# CryptoFlashRTC.net
KiCad netlist of a schematic drawn in EAGLE
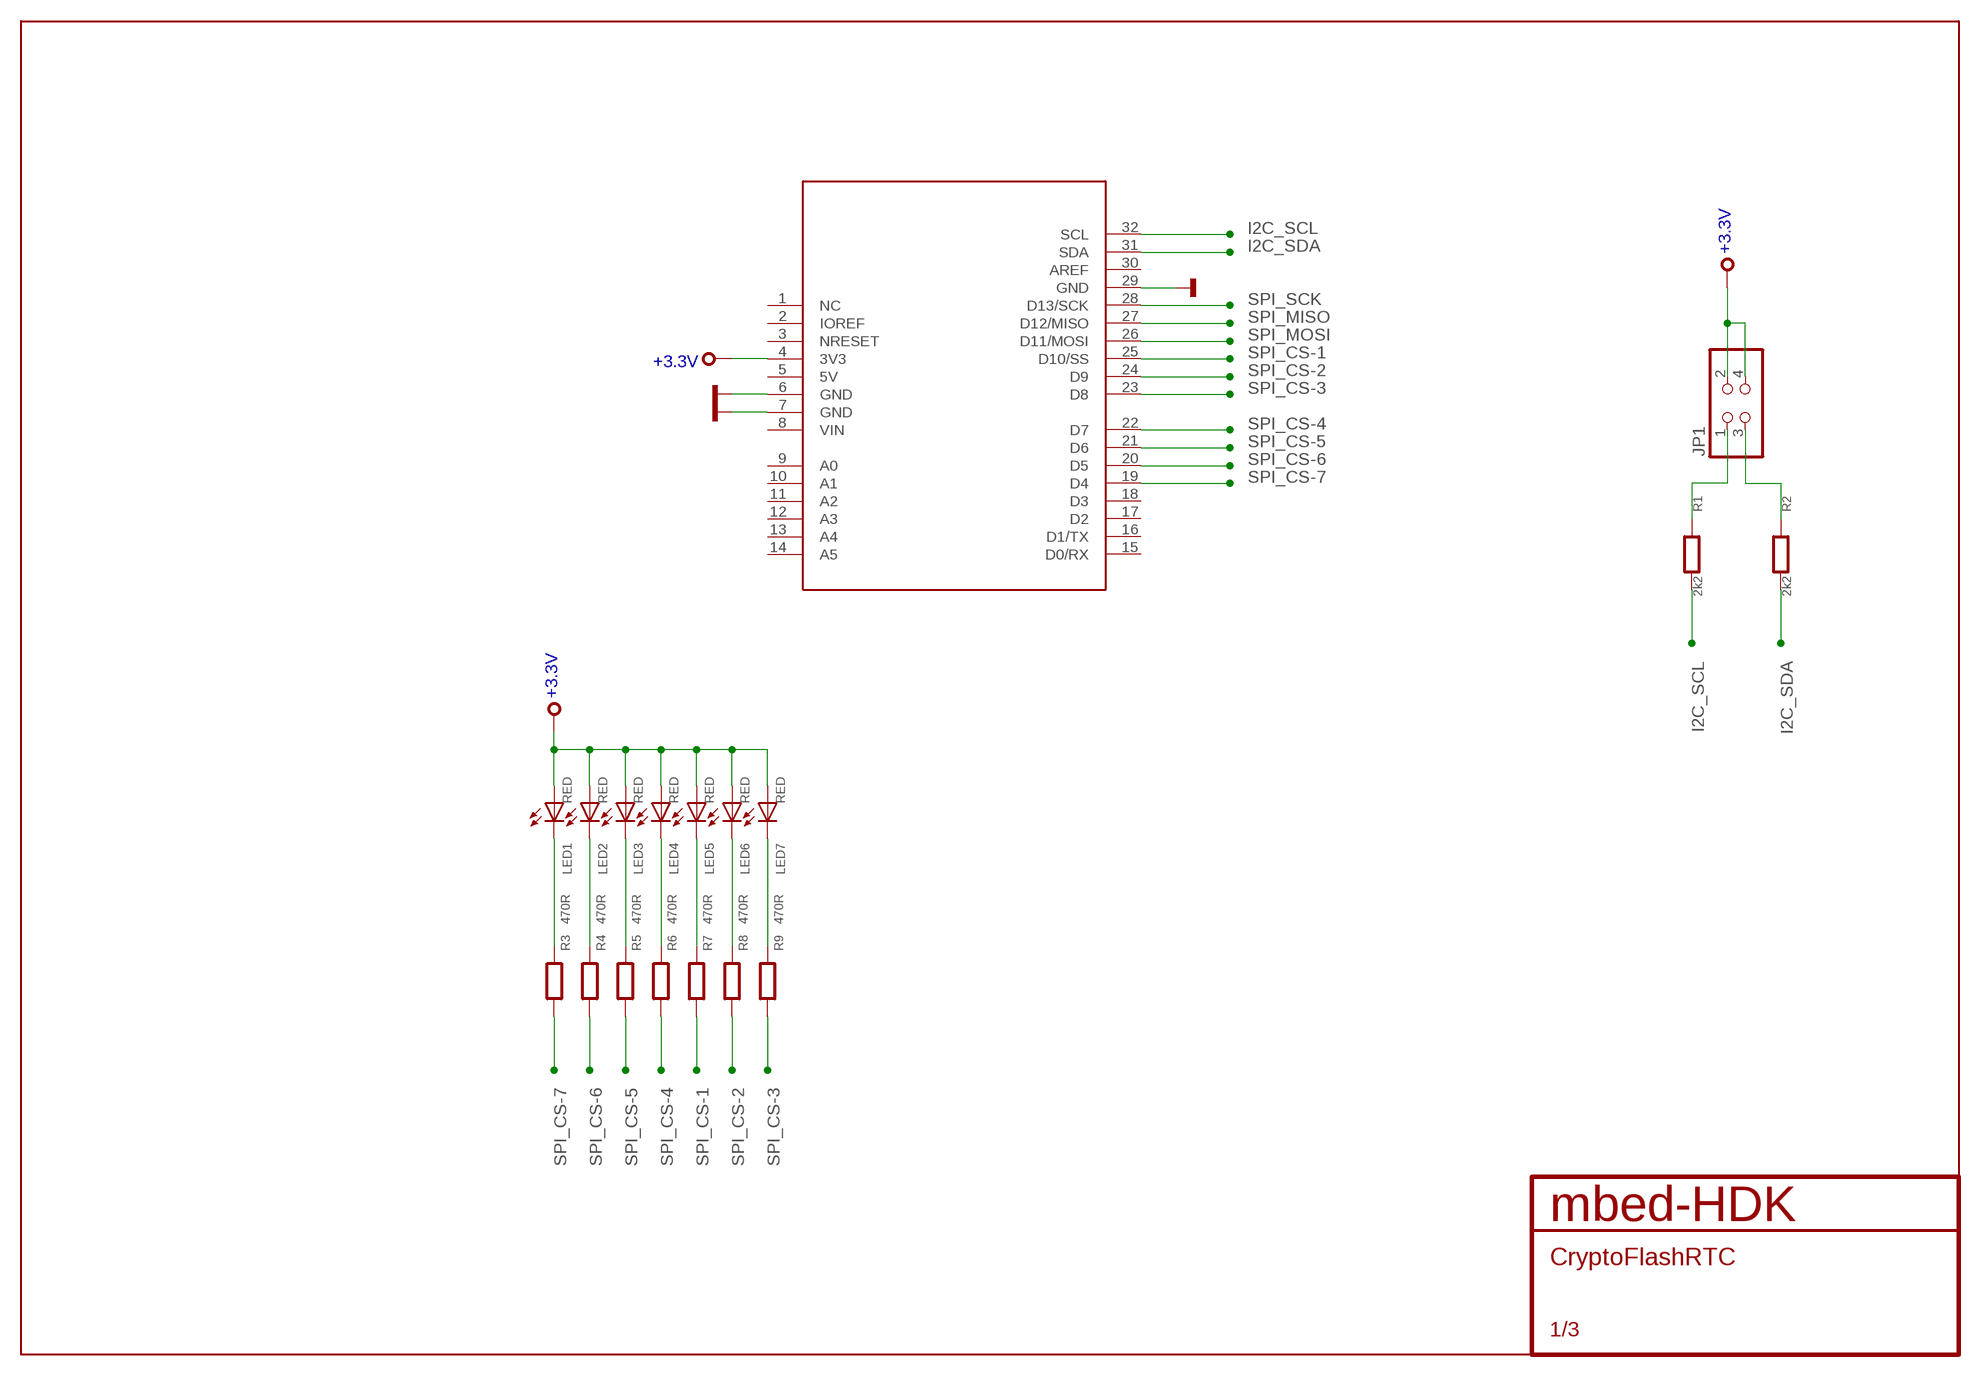
[diagram p0: schematic, sheet 1]
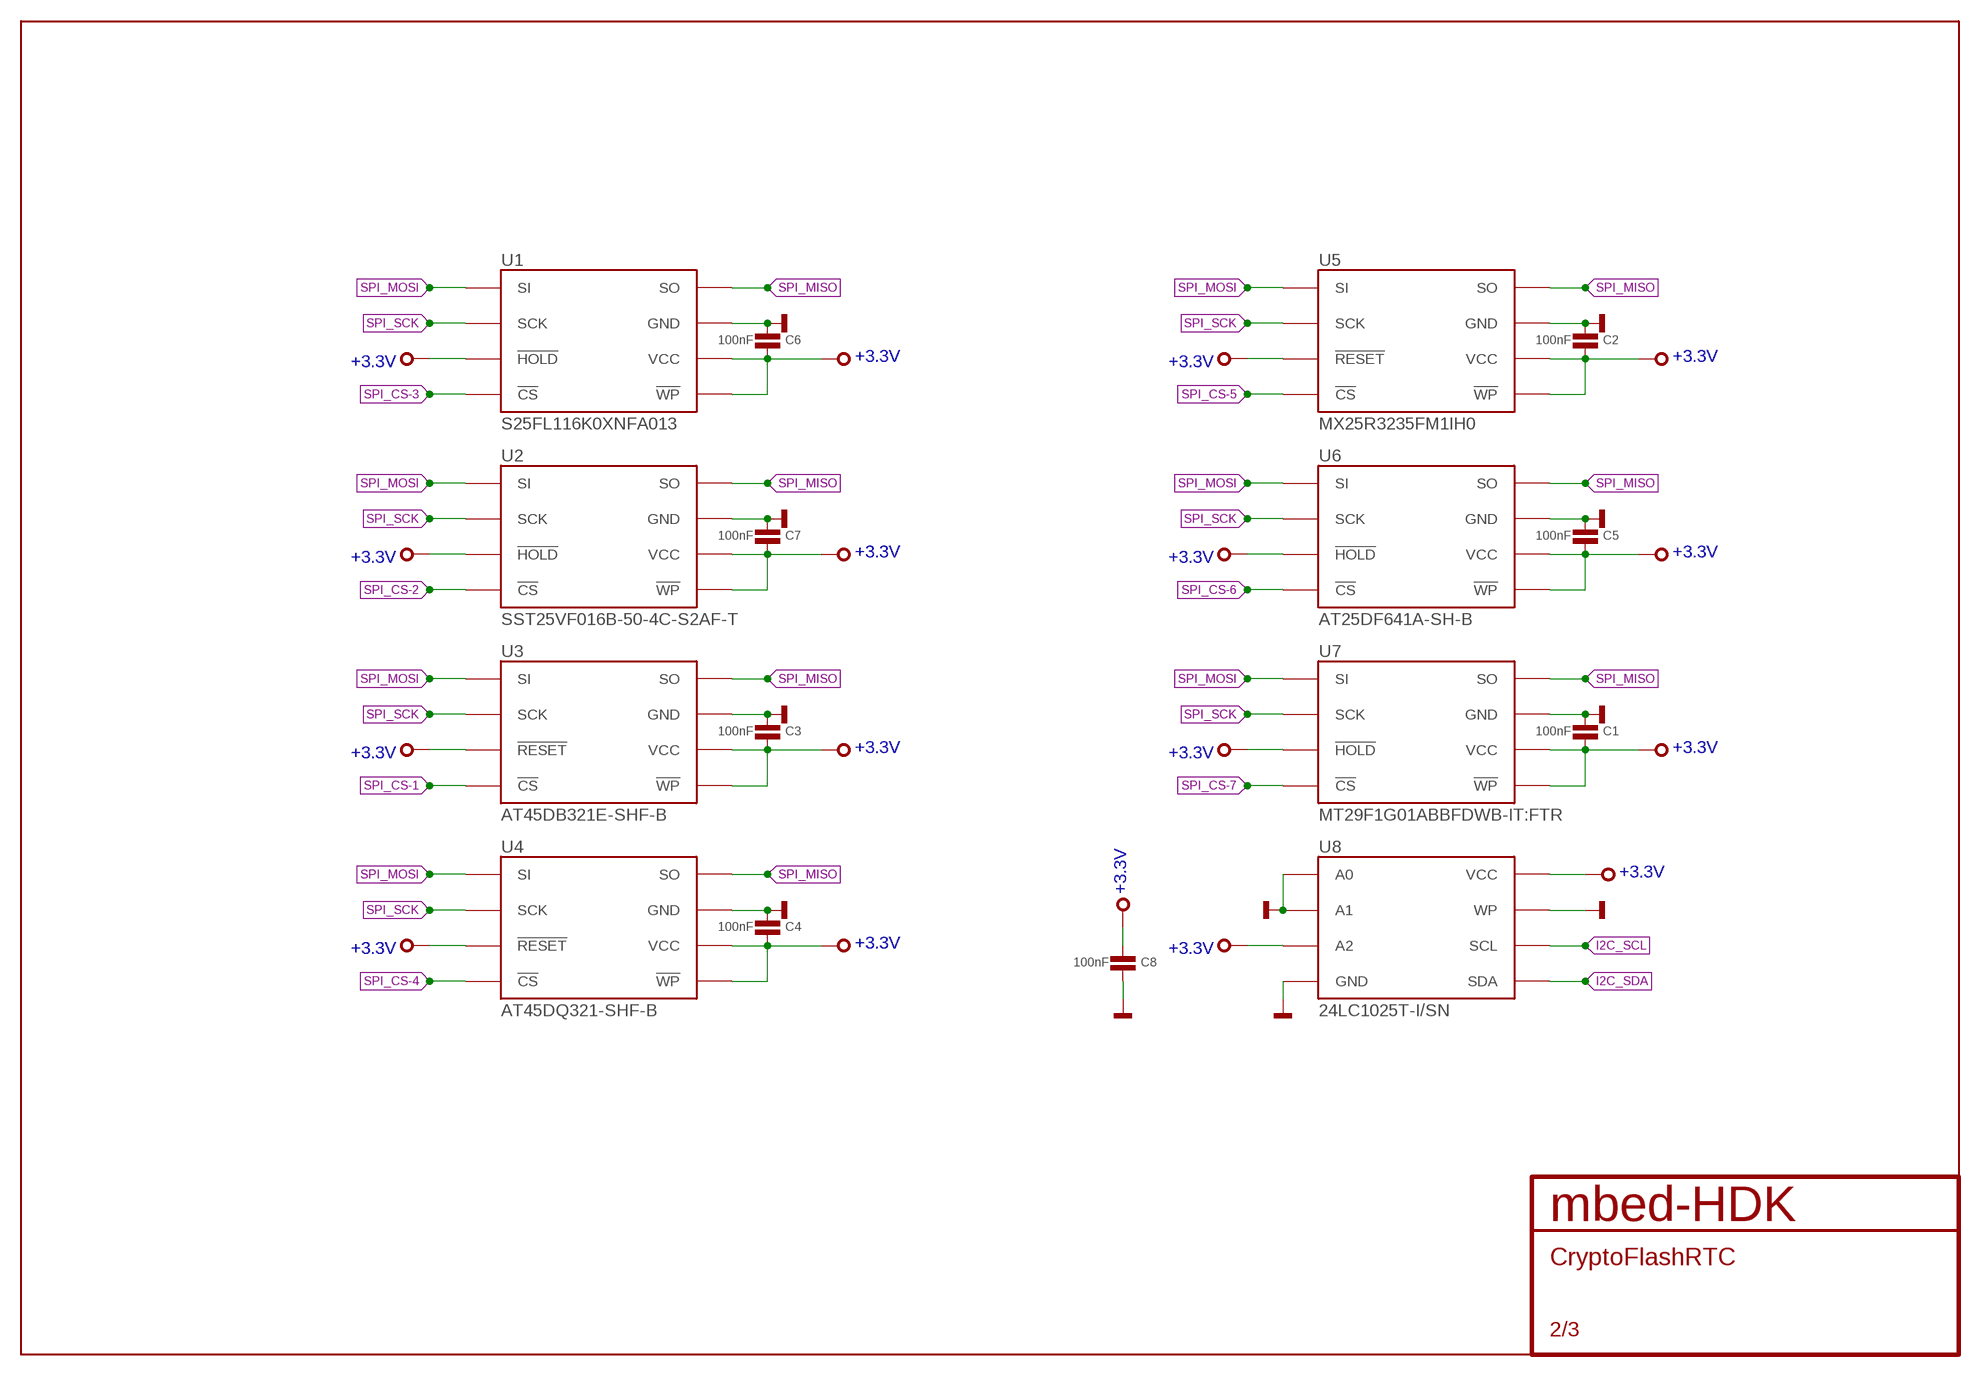
[diagram p1: schematic, sheet 2]
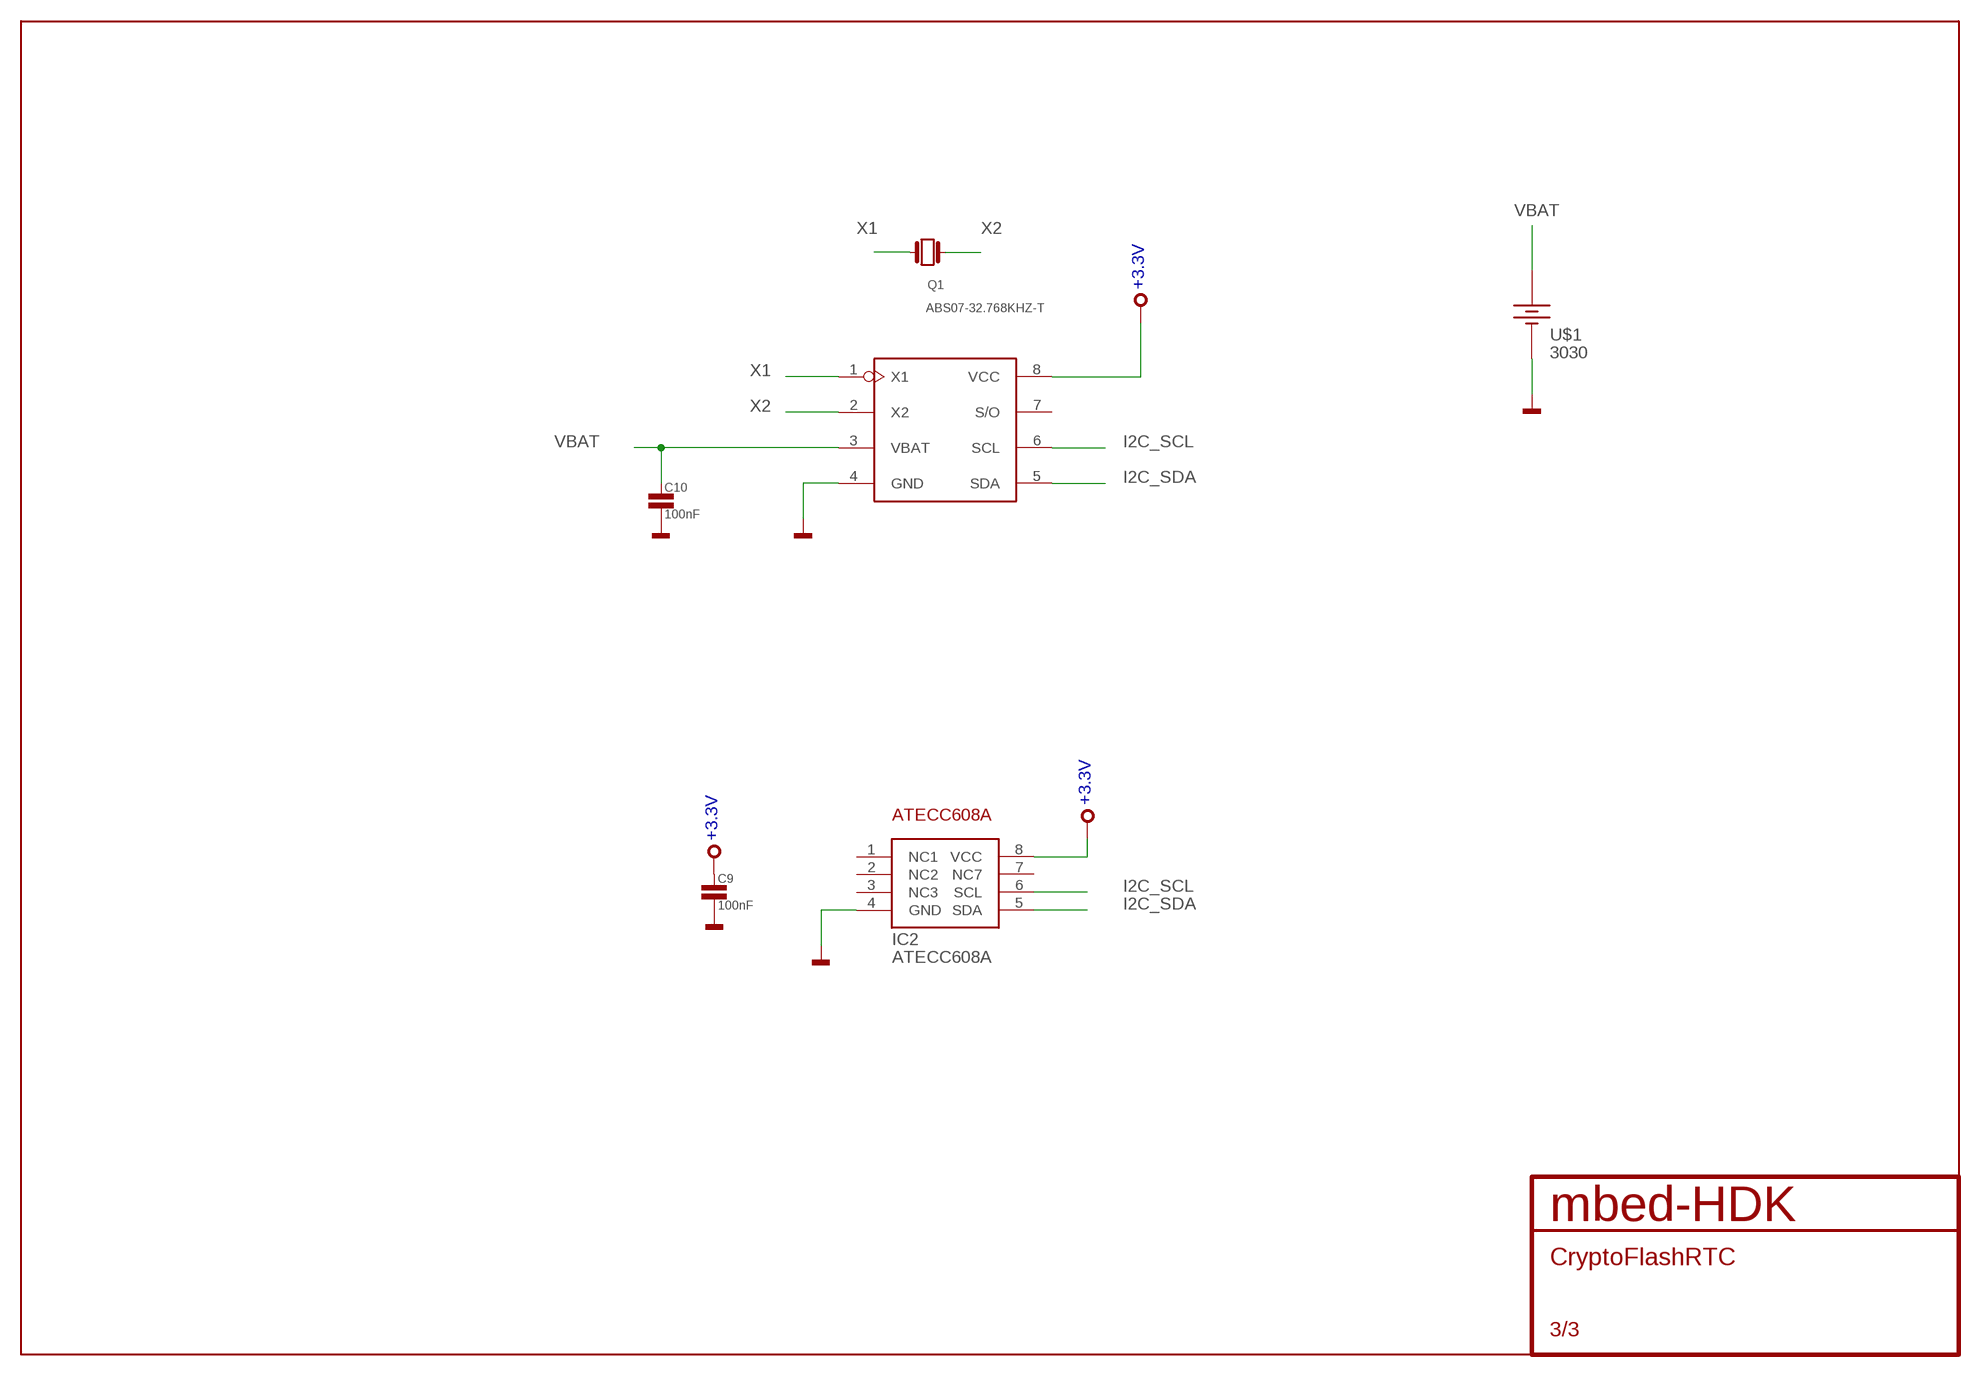
[diagram p2: schematic, sheet 3]

(export (version "E")
  (design (tool "Eeschema 10.0.6"))
  (components
    (comp (ref "C9")
      (value "100nF")
      (footprint "eagle-import:0603")
      (libsource (lib "eagle-import") (part "C0603"))
    )
    (comp (ref "C10")
      (value "100nF")
      (footprint "eagle-import:0603")
      (libsource (lib "eagle-import") (part "C0603"))
    )
    (comp (ref "IC2")
      (value "ATECC608A")
      (footprint "eagle-import:SO8")
      (libsource (lib "eagle-import") (part "ATECC608A"))
    )
    (comp (ref "Q1")
      (value "ABS07-32.768KHZ-T")
      (footprint "eagle-import:FC135")
      (fields (field (name "MF") "Abracon"))
      (libsource (lib "eagle-import") (part "ABS07-32.768KHZ-T"))
    )
    (comp (ref "U$1")
      (value "3030")
      (footprint "eagle-import:3030")
      (fields (field (name "MF") "Keystone"))
      (libsource (lib "eagle-import") (part "3030"))
    )
    (comp (ref "U9")
      (value "DS1307")
      (footprint "eagle-import:SO08")
      (libsource (lib "eagle-import") (part "DS1307"))
    )
    (comp (ref "C1")
      (value "100nF")
      (footprint "eagle-import:0603")
      (libsource (lib "eagle-import") (part "C0603"))
    )
    (comp (ref "C2")
      (value "100nF")
      (footprint "eagle-import:0603")
      (libsource (lib "eagle-import") (part "C0603"))
    )
    (comp (ref "C3")
      (value "100nF")
      (footprint "eagle-import:0603")
      (libsource (lib "eagle-import") (part "C0603"))
    )
    (comp (ref "C4")
      (value "100nF")
      (footprint "eagle-import:0603")
      (libsource (lib "eagle-import") (part "C0603"))
    )
    (comp (ref "C5")
      (value "100nF")
      (footprint "eagle-import:0603")
      (libsource (lib "eagle-import") (part "C0603"))
    )
    (comp (ref "C6")
      (value "100nF")
      (footprint "eagle-import:0603")
      (libsource (lib "eagle-import") (part "C0603"))
    )
    (comp (ref "C7")
      (value "100nF")
      (footprint "eagle-import:0603")
      (libsource (lib "eagle-import") (part "C0603"))
    )
    (comp (ref "C8")
      (value "100nF")
      (footprint "eagle-import:0603")
      (libsource (lib "eagle-import") (part "C0603"))
    )
    (comp (ref "U1")
      (value "S25FL116K0XNFA013")
      (footprint "eagle-import:SO8-WIDE@1")
      (fields (field (name "MF") "Cypress Semiconductor Corp"))
      (libsource (lib "eagle-import") (part "S25FL116K0XNFA013"))
    )
    (comp (ref "U2")
      (value "SST25VF016B-50-4C-S2AF-T")
      (footprint "eagle-import:SO8-WIDE")
      (fields (field (name "MF") "Microchip"))
      (libsource (lib "eagle-import") (part "SST25VF016B-50-4C-S2AF-T"))
    )
    (comp (ref "U3")
      (value "AT45DB321E-SHF-B")
      (footprint "eagle-import:SO8-WIDE")
      (fields (field (name "MF") "Adesto Technologies"))
      (libsource (lib "eagle-import") (part "AT45DB321E-SHF-B"))
    )
    (comp (ref "U4")
      (value "AT45DQ321-SHF-B")
      (footprint "eagle-import:SO8-WIDE")
      (fields (field (name "MF") "Adesto Technologies"))
      (libsource (lib "eagle-import") (part "AT45DQ321-SHF-B"))
    )
    (comp (ref "U5")
      (value "MX25R3235FM1IH0")
      (footprint "eagle-import:SO8")
      (fields (field (name "MF") "Macronix"))
      (libsource (lib "eagle-import") (part "MX25R3235FM1IH0"))
    )
    (comp (ref "U6")
      (value "AT25DF641A-SH-B")
      (footprint "eagle-import:SO8-WIDE")
      (fields (field (name "MF") "Adesto Technologies"))
      (libsource (lib "eagle-import") (part "AT25DF641A-SH-B"))
    )
    (comp (ref "U7")
      (value "MT29F1G01ABBFDWB-IT:FTR")
      (footprint "eagle-import:8-U-PDFN")
      (fields (field (name "MF") "Micron Technology Inc."))
      (libsource (lib "eagle-import") (part "MT29F1G01ABBFDWB-IT{colon}FTR"))
    )
    (comp (ref "U8")
      (value "24LC1025T-I/SN")
      (footprint "eagle-import:SO8")
      (fields (field (name "MF") "Microchip Technology"))
      (libsource (lib "eagle-import") (part "24LC1025T-I/SN"))
    )
    (comp (ref "BRD1")
      (value "K64F/K22F-SHIELD")
      (footprint "eagle-import:K64F_K22F")
      (libsource (lib "eagle-import") (part "K64F/K22F-SHIELD"))
    )
    (comp (ref "JP1")
      (value "PINHD-2X2")
      (footprint "eagle-import:2X02")
      (libsource (lib "eagle-import") (part "PINHD-2X2"))
    )
    (comp (ref "LED1")
      (value "RED")
      (footprint "eagle-import:CHIPLED_0603")
      (fields (field (name "MF") "Wurth Electronics Inc"))
      (libsource (lib "eagle-import") (part "SMD_LED0603"))
    )
    (comp (ref "LED2")
      (value "RED")
      (footprint "eagle-import:CHIPLED_0603")
      (fields (field (name "MF") "Wurth Electronics Inc"))
      (libsource (lib "eagle-import") (part "SMD_LED0603"))
    )
    (comp (ref "LED3")
      (value "RED")
      (footprint "eagle-import:CHIPLED_0603")
      (fields (field (name "MF") "Wurth Electronics Inc"))
      (libsource (lib "eagle-import") (part "SMD_LED0603"))
    )
    (comp (ref "LED4")
      (value "RED")
      (footprint "eagle-import:CHIPLED_0603")
      (fields (field (name "MF") "Wurth Electronics Inc"))
      (libsource (lib "eagle-import") (part "SMD_LED0603"))
    )
    (comp (ref "LED5")
      (value "RED")
      (footprint "eagle-import:CHIPLED_0603")
      (fields (field (name "MF") "Wurth Electronics Inc"))
      (libsource (lib "eagle-import") (part "SMD_LED0603"))
    )
    (comp (ref "LED6")
      (value "RED")
      (footprint "eagle-import:CHIPLED_0603")
      (fields (field (name "MF") "Wurth Electronics Inc"))
      (libsource (lib "eagle-import") (part "SMD_LED0603"))
    )
    (comp (ref "LED7")
      (value "RED")
      (footprint "eagle-import:CHIPLED_0603")
      (fields (field (name "MF") "Wurth Electronics Inc"))
      (libsource (lib "eagle-import") (part "SMD_LED0603"))
    )
    (comp (ref "R1")
      (value "2k2")
      (footprint "eagle-import:0603")
      (libsource (lib "eagle-import") (part "R0603"))
    )
    (comp (ref "R2")
      (value "2k2")
      (footprint "eagle-import:0603")
      (libsource (lib "eagle-import") (part "R0603"))
    )
    (comp (ref "R3")
      (value "470R")
      (footprint "eagle-import:0603")
      (libsource (lib "eagle-import") (part "R0603"))
    )
    (comp (ref "R4")
      (value "470R")
      (footprint "eagle-import:0603")
      (libsource (lib "eagle-import") (part "R0603"))
    )
    (comp (ref "R5")
      (value "470R")
      (footprint "eagle-import:0603")
      (libsource (lib "eagle-import") (part "R0603"))
    )
    (comp (ref "R6")
      (value "470R")
      (footprint "eagle-import:0603")
      (libsource (lib "eagle-import") (part "R0603"))
    )
    (comp (ref "R7")
      (value "470R")
      (footprint "eagle-import:0603")
      (libsource (lib "eagle-import") (part "R0603"))
    )
    (comp (ref "R8")
      (value "470R")
      (footprint "eagle-import:0603")
      (libsource (lib "eagle-import") (part "RESISTOR0603"))
    )
    (comp (ref "R9")
      (value "470R")
      (footprint "eagle-import:0603")
      (libsource (lib "eagle-import") (part "R0603"))
    )
  )
  (nets
    (net (code "1") (name "+3.3V") (class "Default")
      (node (ref "BRD1") (pin "4") (pinfunction "3V3_4") (pintype "bidirectional"))
      (node (ref "C1") (pin "1") (pinfunction "P$1_1") (pintype "passive"))
      (node (ref "C2") (pin "1") (pinfunction "P$1_1") (pintype "passive"))
      (node (ref "C3") (pin "1") (pinfunction "P$1_1") (pintype "passive"))
      (node (ref "C4") (pin "1") (pinfunction "P$1_1") (pintype "passive"))
      (node (ref "C5") (pin "1") (pinfunction "P$1_1") (pintype "passive"))
      (node (ref "C6") (pin "1") (pinfunction "P$1_1") (pintype "passive"))
      (node (ref "C7") (pin "1") (pinfunction "P$1_1") (pintype "passive"))
      (node (ref "C8") (pin "2") (pinfunction "P$2_2") (pintype "passive"))
      (node (ref "C9") (pin "1") (pinfunction "P$1_1") (pintype "passive"))
      (node (ref "IC2") (pin "8") (pinfunction "VCC_8") (pintype "bidirectional"))
      (node (ref "JP1") (pin "2") (pinfunction "2_2") (pintype "passive"))
      (node (ref "JP1") (pin "4") (pinfunction "4_4") (pintype "passive"))
      (node (ref "LED1") (pin "A") (pinfunction "A_A") (pintype "passive"))
      (node (ref "LED2") (pin "A") (pinfunction "A_A") (pintype "passive"))
      (node (ref "LED3") (pin "A") (pinfunction "A_A") (pintype "passive"))
      (node (ref "LED4") (pin "A") (pinfunction "A_A") (pintype "passive"))
      (node (ref "LED5") (pin "A") (pinfunction "A_A") (pintype "passive"))
      (node (ref "LED6") (pin "A") (pinfunction "A_A") (pintype "passive"))
      (node (ref "LED7") (pin "A") (pinfunction "A_A") (pintype "passive"))
      (node (ref "U1") (pin "3") (pinfunction "~{WP}_3") (pintype "bidirectional"))
      (node (ref "U1") (pin "7") (pinfunction "~{HOLD}_7") (pintype "bidirectional"))
      (node (ref "U1") (pin "8") (pinfunction "VCC_8") (pintype "bidirectional"))
      (node (ref "U2") (pin "3") (pinfunction "~{WP}_3") (pintype "bidirectional"))
      (node (ref "U2") (pin "7") (pinfunction "~{HOLD}_7") (pintype "bidirectional"))
      (node (ref "U2") (pin "8") (pinfunction "VCC_8") (pintype "bidirectional"))
      (node (ref "U3") (pin "3") (pinfunction "~{RESET}_3") (pintype "bidirectional"))
      (node (ref "U3") (pin "5") (pinfunction "~{WP}_5") (pintype "bidirectional"))
      (node (ref "U3") (pin "6") (pinfunction "VCC_6") (pintype "bidirectional"))
      (node (ref "U4") (pin "3") (pinfunction "~{RESET}_3") (pintype "bidirectional"))
      (node (ref "U4") (pin "5") (pinfunction "~{WP}_5") (pintype "bidirectional"))
      (node (ref "U4") (pin "6") (pinfunction "VCC_6") (pintype "bidirectional"))
      (node (ref "U5") (pin "3") (pinfunction "~{WP}_3") (pintype "bidirectional"))
      (node (ref "U5") (pin "7") (pinfunction "~{RESET}_7") (pintype "bidirectional"))
      (node (ref "U5") (pin "8") (pinfunction "VCC_8") (pintype "bidirectional"))
      (node (ref "U6") (pin "3") (pinfunction "~{WP}_3") (pintype "bidirectional"))
      (node (ref "U6") (pin "7") (pinfunction "~{HOLD}_7") (pintype "bidirectional"))
      (node (ref "U6") (pin "8") (pinfunction "VCC_8") (pintype "bidirectional"))
      (node (ref "U7") (pin "3") (pinfunction "~{WP}_3") (pintype "bidirectional"))
      (node (ref "U7") (pin "7") (pinfunction "~{HOLD}_7") (pintype "bidirectional"))
      (node (ref "U7") (pin "8") (pinfunction "VCC_8") (pintype "bidirectional"))
      (node (ref "U8") (pin "3") (pinfunction "A2_3") (pintype "bidirectional"))
      (node (ref "U8") (pin "8") (pinfunction "VCC_8") (pintype "bidirectional"))
      (node (ref "U9") (pin "8") (pinfunction "VCC_8") (pintype "bidirectional"))
    )
    (net (code "2") (name "GND") (class "Default")
      (node (ref "BRD1") (pin "29") (pinfunction "GND_29") (pintype "bidirectional"))
      (node (ref "BRD1") (pin "6") (pinfunction "GND_6") (pintype "bidirectional"))
      (node (ref "BRD1") (pin "7") (pinfunction "GND_7") (pintype "bidirectional"))
      (node (ref "C1") (pin "2") (pinfunction "P$2_2") (pintype "passive"))
      (node (ref "C10") (pin "2") (pinfunction "P$2_2") (pintype "passive"))
      (node (ref "C2") (pin "2") (pinfunction "P$2_2") (pintype "passive"))
      (node (ref "C3") (pin "2") (pinfunction "P$2_2") (pintype "passive"))
      (node (ref "C4") (pin "2") (pinfunction "P$2_2") (pintype "passive"))
      (node (ref "C5") (pin "2") (pinfunction "P$2_2") (pintype "passive"))
      (node (ref "C6") (pin "2") (pinfunction "P$2_2") (pintype "passive"))
      (node (ref "C7") (pin "2") (pinfunction "P$2_2") (pintype "passive"))
      (node (ref "C8") (pin "1") (pinfunction "P$1_1") (pintype "passive"))
      (node (ref "C9") (pin "2") (pinfunction "P$2_2") (pintype "passive"))
      (node (ref "IC2") (pin "4") (pinfunction "GND_4") (pintype "bidirectional"))
      (node (ref "U$1") (pin "NEG") (pinfunction "-_NEG") (pintype "bidirectional"))
      (node (ref "U1") (pin "4") (pinfunction "GND_4") (pintype "bidirectional"))
      (node (ref "U2") (pin "4") (pinfunction "GND_4") (pintype "bidirectional"))
      (node (ref "U3") (pin "7") (pinfunction "GND_7") (pintype "bidirectional"))
      (node (ref "U4") (pin "7") (pinfunction "GND_7") (pintype "bidirectional"))
      (node (ref "U5") (pin "4") (pinfunction "GND_4") (pintype "bidirectional"))
      (node (ref "U6") (pin "4") (pinfunction "GND_4") (pintype "bidirectional"))
      (node (ref "U7") (pin "4") (pinfunction "GND_4") (pintype "bidirectional"))
      (node (ref "U8") (pin "1") (pinfunction "A0_1") (pintype "bidirectional"))
      (node (ref "U8") (pin "2") (pinfunction "A1_2") (pintype "bidirectional"))
      (node (ref "U8") (pin "4") (pinfunction "GND_4") (pintype "bidirectional"))
      (node (ref "U8") (pin "7") (pinfunction "WP_7") (pintype "bidirectional"))
      (node (ref "U9") (pin "4") (pinfunction "GND_4") (pintype "bidirectional"))
    )
    (net (code "3") (name "I2C_SCL") (class "Default")
      (node (ref "BRD1") (pin "32") (pinfunction "SCL_32") (pintype "bidirectional"))
      (node (ref "IC2") (pin "6") (pinfunction "SCL_6") (pintype "bidirectional"))
      (node (ref "R1") (pin "2") (pinfunction "P$2_2") (pintype "passive"))
      (node (ref "U8") (pin "6") (pinfunction "SCL_6") (pintype "bidirectional"))
      (node (ref "U9") (pin "6") (pinfunction "SCL_6") (pintype "bidirectional"))
    )
    (net (code "4") (name "I2C_SDA") (class "Default")
      (node (ref "BRD1") (pin "31") (pinfunction "SDA_31") (pintype "bidirectional"))
      (node (ref "IC2") (pin "5") (pinfunction "SDA_5") (pintype "bidirectional"))
      (node (ref "R2") (pin "2") (pinfunction "P$2_2") (pintype "passive"))
      (node (ref "U8") (pin "5") (pinfunction "SDA_5") (pintype "bidirectional"))
      (node (ref "U9") (pin "5") (pinfunction "SDA_5") (pintype "bidirectional"))
    )
    (net (code "5") (name "Net-(R1-P$1)") (class "Default")
      (node (ref "JP1") (pin "1") (pinfunction "1_1") (pintype "passive"))
      (node (ref "R1") (pin "1") (pinfunction "P$1_1") (pintype "passive"))
    )
    (net (code "6") (name "Net-(R2-P$1)") (class "Default")
      (node (ref "JP1") (pin "3") (pinfunction "3_3") (pintype "passive"))
      (node (ref "R2") (pin "1") (pinfunction "P$1_1") (pintype "passive"))
    )
    (net (code "7") (name "Net-(R3-P$1)") (class "Default")
      (node (ref "LED1") (pin "C") (pinfunction "C_C") (pintype "passive"))
      (node (ref "R3") (pin "1") (pinfunction "P$1_1") (pintype "passive"))
    )
    (net (code "8") (name "Net-(R4-P$1)") (class "Default")
      (node (ref "LED2") (pin "C") (pinfunction "C_C") (pintype "passive"))
      (node (ref "R4") (pin "1") (pinfunction "P$1_1") (pintype "passive"))
    )
    (net (code "9") (name "Net-(R5-P$1)") (class "Default")
      (node (ref "LED3") (pin "C") (pinfunction "C_C") (pintype "passive"))
      (node (ref "R5") (pin "1") (pinfunction "P$1_1") (pintype "passive"))
    )
    (net (code "10") (name "Net-(R6-P$1)") (class "Default")
      (node (ref "LED4") (pin "C") (pinfunction "C_C") (pintype "passive"))
      (node (ref "R6") (pin "1") (pinfunction "P$1_1") (pintype "passive"))
    )
    (net (code "11") (name "Net-(R7-P$1)") (class "Default")
      (node (ref "LED5") (pin "C") (pinfunction "C_C") (pintype "passive"))
      (node (ref "R7") (pin "1") (pinfunction "P$1_1") (pintype "passive"))
    )
    (net (code "12") (name "Net-(R8-P$1)") (class "Default")
      (node (ref "LED6") (pin "C") (pinfunction "C_C") (pintype "passive"))
      (node (ref "R8") (pin "1") (pinfunction "P$1_1") (pintype "passive"))
    )
    (net (code "13") (name "Net-(R9-P$1)") (class "Default")
      (node (ref "LED7") (pin "C") (pinfunction "C_C") (pintype "passive"))
      (node (ref "R9") (pin "1") (pinfunction "P$1_1") (pintype "passive"))
    )
    (net (code "14") (name "SPI_CS-1") (class "Default")
      (node (ref "BRD1") (pin "25") (pinfunction "D10/SS_25") (pintype "bidirectional"))
      (node (ref "R7") (pin "2") (pinfunction "P$2_2") (pintype "passive"))
      (node (ref "U3") (pin "4") (pinfunction "~{CS}_4") (pintype "bidirectional"))
    )
    (net (code "15") (name "SPI_CS-2") (class "Default")
      (node (ref "BRD1") (pin "24") (pinfunction "D9_24") (pintype "bidirectional"))
      (node (ref "R8") (pin "2") (pinfunction "P$2_2") (pintype "passive"))
      (node (ref "U2") (pin "1") (pinfunction "~{CS}_1") (pintype "bidirectional"))
    )
    (net (code "16") (name "SPI_CS-3") (class "Default")
      (node (ref "BRD1") (pin "23") (pinfunction "D8_23") (pintype "bidirectional"))
      (node (ref "R9") (pin "2") (pinfunction "P$2_2") (pintype "passive"))
      (node (ref "U1") (pin "1") (pinfunction "~{CS}_1") (pintype "bidirectional"))
    )
    (net (code "17") (name "SPI_CS-4") (class "Default")
      (node (ref "BRD1") (pin "22") (pinfunction "D7_22") (pintype "bidirectional"))
      (node (ref "R6") (pin "2") (pinfunction "P$2_2") (pintype "passive"))
      (node (ref "U4") (pin "4") (pinfunction "~{CS}_4") (pintype "bidirectional"))
    )
    (net (code "18") (name "SPI_CS-5") (class "Default")
      (node (ref "BRD1") (pin "21") (pinfunction "D6_21") (pintype "bidirectional"))
      (node (ref "R5") (pin "2") (pinfunction "P$2_2") (pintype "passive"))
      (node (ref "U5") (pin "1") (pinfunction "~{CS}_1") (pintype "bidirectional"))
    )
    (net (code "19") (name "SPI_CS-6") (class "Default")
      (node (ref "BRD1") (pin "20") (pinfunction "D5_20") (pintype "bidirectional"))
      (node (ref "R4") (pin "2") (pinfunction "P$2_2") (pintype "passive"))
      (node (ref "U6") (pin "1") (pinfunction "~{CS}_1") (pintype "bidirectional"))
    )
    (net (code "20") (name "SPI_CS-7") (class "Default")
      (node (ref "BRD1") (pin "19") (pinfunction "D4_19") (pintype "bidirectional"))
      (node (ref "R3") (pin "2") (pinfunction "P$2_2") (pintype "passive"))
      (node (ref "U7") (pin "1") (pinfunction "~{CS}_1") (pintype "bidirectional"))
    )
    (net (code "21") (name "SPI_MISO") (class "Default")
      (node (ref "BRD1") (pin "27") (pinfunction "D12/MISO_27") (pintype "bidirectional"))
      (node (ref "U1") (pin "2") (pinfunction "SO_2") (pintype "bidirectional"))
      (node (ref "U2") (pin "2") (pinfunction "SO_2") (pintype "bidirectional"))
      (node (ref "U3") (pin "8") (pinfunction "SO_8") (pintype "bidirectional"))
      (node (ref "U4") (pin "8") (pinfunction "SO_8") (pintype "bidirectional"))
      (node (ref "U5") (pin "2") (pinfunction "SO_2") (pintype "bidirectional"))
      (node (ref "U6") (pin "2") (pinfunction "SO_2") (pintype "bidirectional"))
      (node (ref "U7") (pin "2") (pinfunction "SO_2") (pintype "bidirectional"))
    )
    (net (code "22") (name "SPI_MOSI") (class "Default")
      (node (ref "BRD1") (pin "26") (pinfunction "D11/MOSI_26") (pintype "bidirectional"))
      (node (ref "U1") (pin "5") (pinfunction "SI_5") (pintype "bidirectional"))
      (node (ref "U2") (pin "5") (pinfunction "SI_5") (pintype "bidirectional"))
      (node (ref "U3") (pin "1") (pinfunction "SI_1") (pintype "bidirectional"))
      (node (ref "U4") (pin "1") (pinfunction "SI_1") (pintype "bidirectional"))
      (node (ref "U5") (pin "5") (pinfunction "SI_5") (pintype "bidirectional"))
      (node (ref "U6") (pin "5") (pinfunction "SI_5") (pintype "bidirectional"))
      (node (ref "U7") (pin "5") (pinfunction "SI_5") (pintype "bidirectional"))
    )
    (net (code "23") (name "SPI_SCK") (class "Default")
      (node (ref "BRD1") (pin "28") (pinfunction "D13/SCK_28") (pintype "bidirectional"))
      (node (ref "U1") (pin "6") (pinfunction "SCK_6") (pintype "bidirectional"))
      (node (ref "U2") (pin "6") (pinfunction "SCK_6") (pintype "bidirectional"))
      (node (ref "U3") (pin "2") (pinfunction "SCK_2") (pintype "bidirectional"))
      (node (ref "U4") (pin "2") (pinfunction "SCK_2") (pintype "bidirectional"))
      (node (ref "U5") (pin "6") (pinfunction "SCK_6") (pintype "bidirectional"))
      (node (ref "U6") (pin "6") (pinfunction "SCK_6") (pintype "bidirectional"))
      (node (ref "U7") (pin "6") (pinfunction "SCK_6") (pintype "bidirectional"))
    )
    (net (code "24") (name "VBAT") (class "Default")
      (node (ref "C10") (pin "1") (pinfunction "P$1_1") (pintype "passive"))
      (node (ref "U$1") (pin "P$1") (pinfunction "+_P$1") (pintype "bidirectional"))
      (node (ref "U$1") (pin "P$2") (pinfunction "+_P$2") (pintype "bidirectional"))
      (node (ref "U9") (pin "3") (pinfunction "VBAT_3") (pintype "bidirectional"))
    )
    (net (code "25") (name "X1") (class "Default")
      (node (ref "Q1") (pin "X1") (pinfunction "1_X1") (pintype "passive"))
      (node (ref "U9") (pin "1") (pinfunction "X1_1") (pintype "bidirectional"))
    )
    (net (code "26") (name "X2") (class "Default")
      (node (ref "Q1") (pin "X2") (pinfunction "2_X2") (pintype "passive"))
      (node (ref "U9") (pin "2") (pinfunction "X2_2") (pintype "bidirectional"))
    )
    (net (code "27") (name "unconnected-(BRD1-5V-Pad5)") (class "Default")
      (node (ref "BRD1") (pin "5") (pinfunction "5V_5") (pintype "bidirectional"))
    )
    (net (code "28") (name "unconnected-(BRD1-A0-Pad9)") (class "Default")
      (node (ref "BRD1") (pin "9") (pinfunction "A0_9") (pintype "bidirectional"))
    )
    (net (code "29") (name "unconnected-(BRD1-A1-Pad10)") (class "Default")
      (node (ref "BRD1") (pin "10") (pinfunction "A1_10") (pintype "bidirectional"))
    )
    (net (code "30") (name "unconnected-(BRD1-A2-Pad11)") (class "Default")
      (node (ref "BRD1") (pin "11") (pinfunction "A2_11") (pintype "bidirectional"))
    )
    (net (code "31") (name "unconnected-(BRD1-A3-Pad12)") (class "Default")
      (node (ref "BRD1") (pin "12") (pinfunction "A3_12") (pintype "bidirectional"))
    )
    (net (code "32") (name "unconnected-(BRD1-A4-Pad13)") (class "Default")
      (node (ref "BRD1") (pin "13") (pinfunction "A4_13") (pintype "bidirectional"))
    )
    (net (code "33") (name "unconnected-(BRD1-A5-Pad14)") (class "Default")
      (node (ref "BRD1") (pin "14") (pinfunction "A5_14") (pintype "bidirectional"))
    )
    (net (code "34") (name "unconnected-(BRD1-AREF-Pad30)") (class "Default")
      (node (ref "BRD1") (pin "30") (pinfunction "AREF_30") (pintype "bidirectional"))
    )
    (net (code "35") (name "unconnected-(BRD1-D0{slash}RX-Pad15)") (class "Default")
      (node (ref "BRD1") (pin "15") (pinfunction "D0/RX_15") (pintype "bidirectional"))
    )
    (net (code "36") (name "unconnected-(BRD1-D1{slash}TX-Pad16)") (class "Default")
      (node (ref "BRD1") (pin "16") (pinfunction "D1/TX_16") (pintype "bidirectional"))
    )
    (net (code "37") (name "unconnected-(BRD1-D2-Pad17)") (class "Default")
      (node (ref "BRD1") (pin "17") (pinfunction "D2_17") (pintype "bidirectional"))
    )
    (net (code "38") (name "unconnected-(BRD1-D3-Pad18)") (class "Default")
      (node (ref "BRD1") (pin "18") (pinfunction "D3_18") (pintype "bidirectional"))
    )
    (net (code "39") (name "unconnected-(BRD1-IOREF-Pad2)") (class "Default")
      (node (ref "BRD1") (pin "2") (pinfunction "IOREF_2") (pintype "bidirectional"))
    )
    (net (code "40") (name "unconnected-(BRD1-NC-Pad1)") (class "Default")
      (node (ref "BRD1") (pin "1") (pinfunction "NC_1") (pintype "bidirectional"))
    )
    (net (code "41") (name "unconnected-(BRD1-NRESET-Pad3)") (class "Default")
      (node (ref "BRD1") (pin "3") (pinfunction "NRESET_3") (pintype "bidirectional"))
    )
    (net (code "42") (name "unconnected-(BRD1-VIN-Pad8)") (class "Default")
      (node (ref "BRD1") (pin "8") (pinfunction "VIN_8") (pintype "bidirectional"))
    )
    (net (code "43") (name "unconnected-(IC2-NC1-Pad1)") (class "Default")
      (node (ref "IC2") (pin "1") (pinfunction "NC1_1") (pintype "bidirectional"))
    )
    (net (code "44") (name "unconnected-(IC2-NC2-Pad2)") (class "Default")
      (node (ref "IC2") (pin "2") (pinfunction "NC2_2") (pintype "bidirectional"))
    )
    (net (code "45") (name "unconnected-(IC2-NC3-Pad3)") (class "Default")
      (node (ref "IC2") (pin "3") (pinfunction "NC3_3") (pintype "bidirectional"))
    )
    (net (code "46") (name "unconnected-(IC2-NC7-Pad7)") (class "Default")
      (node (ref "IC2") (pin "7") (pinfunction "NC7_7") (pintype "bidirectional"))
    )
    (net (code "47") (name "unconnected-(U9-S{slash}O-Pad7)") (class "Default")
      (node (ref "U9") (pin "7") (pinfunction "S/O_7") (pintype "bidirectional"))
    )
  )
)
